# Lower_board.net
KiCad netlist of a schematic drawn in EAGLE
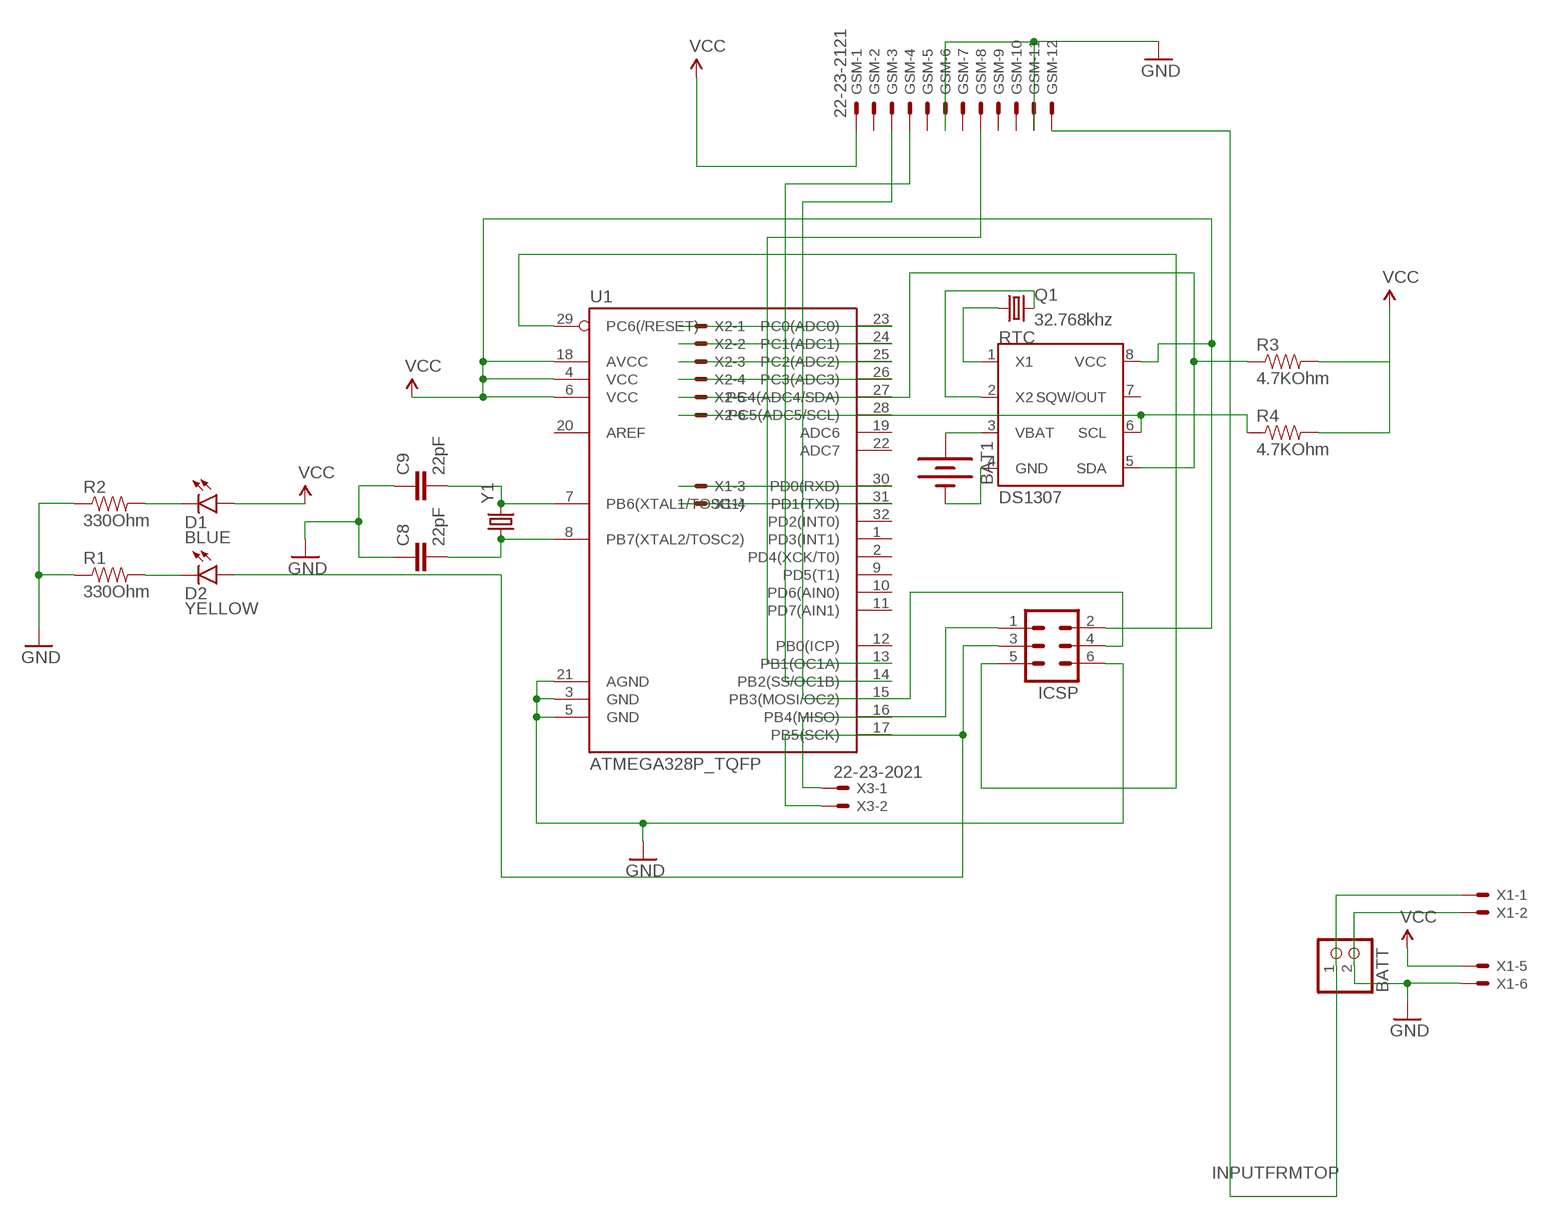
[diagram p0: schematic, sheet 1]

(export (version "E")
  (design (tool "Eeschema 10.0.6"))
  (components
    (comp (ref "BAT1")
      (value "BATTERY20PTH")
      (footprint "eagle-import:BATTCOM_20MM_PTH")
      (libsource (lib "eagle-import") (part "BATTERY20PTH"))
    )
    (comp (ref "BATT")
      (value "JST_2PIN-SMT-RA")
      (footprint "eagle-import:JST-PH-2-SMT-RA")
      (libsource (lib "eagle-import") (part "JST_2PIN-SMT-RA"))
    )
    (comp (ref "C8")
      (value "22pF")
      (footprint "eagle-import:0603-CAP")
      (libsource (lib "eagle-import") (part "CAP0603-CAP"))
    )
    (comp (ref "C9")
      (value "22pF")
      (footprint "eagle-import:0603-CAP")
      (libsource (lib "eagle-import") (part "CAP0603-CAP"))
    )
    (comp (ref "D1")
      (value "BLUE")
      (footprint "eagle-import:LED-1206")
      (libsource (lib "eagle-import") (part "LED-BLUE1206"))
    )
    (comp (ref "D2")
      (value "YELLOW")
      (footprint "eagle-import:LED-1206")
      (libsource (lib "eagle-import") (part "LED-YELLOWLARGE"))
    )
    (comp (ref "GSM")
      (value "22-23-2121")
      (footprint "eagle-import:22-23-2121")
      (fields (field (name "MF") "MOLEX"))
      (libsource (lib "eagle-import") (part "22-23-2121"))
    )
    (comp (ref "ICSP")
      (value "ML6")
      (footprint "eagle-import:ML6")
      (libsource (lib "eagle-import") (part "ML6"))
    )
    (comp (ref "Q1")
      (value "32.768khz")
      (footprint "eagle-import:CRYSTAL-TXC-7A")
      (libsource (lib "eagle-import") (part "CRYSTALTXC-7A"))
    )
    (comp (ref "R1")
      (value "330Ohm")
      (footprint "eagle-import:1206")
      (libsource (lib "eagle-import") (part "RESISTOR1206"))
    )
    (comp (ref "R2")
      (value "330Ohm")
      (footprint "eagle-import:1206")
      (libsource (lib "eagle-import") (part "RESISTOR1206"))
    )
    (comp (ref "R3")
      (value "4.7KOhm")
      (footprint "eagle-import:1206")
      (libsource (lib "eagle-import") (part "RESISTOR1206"))
    )
    (comp (ref "R4")
      (value "4.7KOhm")
      (footprint "eagle-import:1206")
      (libsource (lib "eagle-import") (part "RESISTOR1206"))
    )
    (comp (ref "RTC")
      (value "DS1307")
      (footprint "eagle-import:SOIC-8")
      (libsource (lib "eagle-import") (part "DS1307"))
    )
    (comp (ref "U1")
      (value "ATMEGA328P_TQFP")
      (footprint "eagle-import:TQFP32-08")
      (libsource (lib "eagle-import") (part "ATMEGA328P_TQFP"))
    )
    (comp (ref "X1")
      (value "22-23-2061")
      (footprint "eagle-import:22-23-2061")
      (fields (field (name "MF") "MOLEX"))
      (libsource (lib "eagle-import") (part "22-23-2061"))
    )
    (comp (ref "X2")
      (value "22-23-2061")
      (footprint "eagle-import:22-23-2061")
      (fields (field (name "MF") "MOLEX"))
      (libsource (lib "eagle-import") (part "22-23-2061"))
    )
    (comp (ref "X3")
      (value "22-23-2021")
      (footprint "eagle-import:22-23-2021")
      (fields (field (name "MF") "MOLEX"))
      (libsource (lib "eagle-import") (part "22-23-2021"))
    )
    (comp (ref "Y1")
      (value "CRYSTALTXC-7A")
      (footprint "eagle-import:CRYSTAL-TXC-7A")
      (libsource (lib "eagle-import") (part "CRYSTALTXC-7A"))
    )
  )
  (nets
    (net (code "1") (name "/INPUTFRMTOP") (class "Default")
      (node (ref "BATT") (pin "1") (pinfunction "2_1") (pintype "passive"))
      (node (ref "GSM") (pin "12") (pinfunction "S_12") (pintype "passive"))
      (node (ref "X1") (pin "1") (pinfunction "S_1") (pintype "passive"))
    )
    (net (code "2") (name "GND") (class "Default")
      (node (ref "BATT") (pin "2") (pinfunction "1_2") (pintype "passive"))
      (node (ref "C8") (pin "1") (pinfunction "1_1") (pintype "passive"))
      (node (ref "C9") (pin "1") (pinfunction "1_1") (pintype "passive"))
      (node (ref "GSM") (pin "11") (pinfunction "S_11") (pintype "passive"))
      (node (ref "GSM") (pin "6") (pinfunction "S_6") (pintype "passive"))
      (node (ref "ICSP") (pin "6") (pinfunction "6_6") (pintype "passive"))
      (node (ref "R1") (pin "1") (pinfunction "1_1") (pintype "passive"))
      (node (ref "R2") (pin "1") (pinfunction "1_1") (pintype "passive"))
      (node (ref "U1") (pin "21") (pinfunction "AGND_21") (pintype "bidirectional"))
      (node (ref "U1") (pin "3") (pinfunction "GND_3") (pintype "bidirectional"))
      (node (ref "U1") (pin "5") (pinfunction "GND_5") (pintype "bidirectional"))
      (node (ref "X1") (pin "2") (pinfunction "S_2") (pintype "passive"))
      (node (ref "X1") (pin "6") (pinfunction "S_6") (pintype "passive"))
    )
    (net (code "3") (name "Net-(BAT1-+)") (class "Default")
      (node (ref "BAT1") (pin "1") (pinfunction "+_1") (pintype "power_in"))
      (node (ref "RTC") (pin "3") (pinfunction "VBAT_3") (pintype "power_in"))
    )
    (net (code "4") (name "Net-(BAT1--)") (class "Default")
      (node (ref "BAT1") (pin "2") (pinfunction "-_2") (pintype "power_in"))
      (node (ref "RTC") (pin "4") (pinfunction "GND_4") (pintype "power_in"))
    )
    (net (code "5") (name "Net-(D1-PadC)") (class "Default")
      (node (ref "D1") (pin "C") (pinfunction "C_C") (pintype "passive"))
      (node (ref "R2") (pin "2") (pinfunction "2_2") (pintype "passive"))
    )
    (net (code "6") (name "Net-(D2-PadC)") (class "Default")
      (node (ref "D2") (pin "C") (pinfunction "C_C") (pintype "passive"))
      (node (ref "R1") (pin "2") (pinfunction "2_2") (pintype "passive"))
    )
    (net (code "7") (name "Net-(GSMF-S)") (class "Default")
      (node (ref "GSM") (pin "3") (pinfunction "S_3") (pintype "passive"))
      (node (ref "ICSP") (pin "4") (pinfunction "4_4") (pintype "passive"))
      (node (ref "U1") (pin "15") (pinfunction "PB3(MOSI/OC2)_15") (pintype "bidirectional"))
    )
    (net (code "8") (name "Net-(GSMG-S)") (class "Default")
      (node (ref "GSM") (pin "4") (pinfunction "S_4") (pintype "passive"))
      (node (ref "U1") (pin "14") (pinfunction "PB2(SS/OC1B)_14") (pintype "bidirectional"))
    )
    (net (code "9") (name "Net-(GSMK-S)") (class "Default")
      (node (ref "GSM") (pin "8") (pinfunction "S_8") (pintype "passive"))
      (node (ref "U1") (pin "13") (pinfunction "PB1(OC1A)_13") (pintype "bidirectional"))
    )
    (net (code "10") (name "Net-(Q1-1)") (class "Default")
      (node (ref "Q1") (pin "P$1") (pinfunction "1_P$1") (pintype "passive"))
      (node (ref "RTC") (pin "1") (pinfunction "X1_1") (pintype "input"))
    )
    (net (code "11") (name "Net-(Q1-2)") (class "Default")
      (node (ref "Q1") (pin "P$2") (pinfunction "2_P$2") (pintype "passive"))
      (node (ref "RTC") (pin "2") (pinfunction "X2_2") (pintype "output"))
    )
    (net (code "12") (name "Net-(RTC-SCL)") (class "Default")
      (node (ref "R4") (pin "1") (pinfunction "1_1") (pintype "passive"))
      (node (ref "RTC") (pin "6") (pinfunction "SCL_6") (pintype "input"))
      (node (ref "U1") (pin "28") (pinfunction "PC5(ADC5/SCL)_28") (pintype "bidirectional"))
      (node (ref "X2") (pin "6") (pinfunction "S_6") (pintype "passive"))
    )
    (net (code "13") (name "Net-(RTC-SDA)") (class "Default")
      (node (ref "R3") (pin "1") (pinfunction "1_1") (pintype "passive"))
      (node (ref "RTC") (pin "5") (pinfunction "SDA_5") (pintype "bidirectional"))
      (node (ref "U1") (pin "27") (pinfunction "PC4(ADC4/SDA)_27") (pintype "bidirectional"))
      (node (ref "X2") (pin "5") (pinfunction "S_5") (pintype "passive"))
    )
    (net (code "14") (name "Net-(U1-PB4(MISO))") (class "Default")
      (node (ref "ICSP") (pin "1") (pinfunction "1_1") (pintype "passive"))
      (node (ref "U1") (pin "16") (pinfunction "PB4(MISO)_16") (pintype "bidirectional"))
      (node (ref "X3") (pin "1") (pinfunction "S_1") (pintype "passive"))
    )
    (net (code "15") (name "Net-(U1-PB6(XTAL1{slash}TOSC1))") (class "Default")
      (node (ref "C9") (pin "2") (pinfunction "2_2") (pintype "passive"))
      (node (ref "U1") (pin "7") (pinfunction "PB6(XTAL1/TOSC1)_7") (pintype "bidirectional"))
      (node (ref "Y1") (pin "P$2") (pinfunction "2_P$2") (pintype "passive"))
    )
    (net (code "16") (name "Net-(U1-PB7(XTAL2{slash}TOSC2))") (class "Default")
      (node (ref "C8") (pin "2") (pinfunction "2_2") (pintype "passive"))
      (node (ref "U1") (pin "8") (pinfunction "PB7(XTAL2/TOSC2)_8") (pintype "bidirectional"))
      (node (ref "Y1") (pin "P$1") (pinfunction "1_P$1") (pintype "passive"))
    )
    (net (code "17") (name "Net-(U1-PC0(ADC0))") (class "Default")
      (node (ref "U1") (pin "23") (pinfunction "PC0(ADC0)_23") (pintype "bidirectional"))
      (node (ref "X2") (pin "1") (pinfunction "S_1") (pintype "passive"))
    )
    (net (code "18") (name "Net-(U1-PC1(ADC1))") (class "Default")
      (node (ref "U1") (pin "24") (pinfunction "PC1(ADC1)_24") (pintype "bidirectional"))
      (node (ref "X2") (pin "2") (pinfunction "S_2") (pintype "passive"))
    )
    (net (code "19") (name "Net-(U1-PC2(ADC2))") (class "Default")
      (node (ref "U1") (pin "25") (pinfunction "PC2(ADC2)_25") (pintype "bidirectional"))
      (node (ref "X2") (pin "3") (pinfunction "S_3") (pintype "passive"))
    )
    (net (code "20") (name "Net-(U1-PC3(ADC3))") (class "Default")
      (node (ref "U1") (pin "26") (pinfunction "PC3(ADC3)_26") (pintype "bidirectional"))
      (node (ref "X2") (pin "4") (pinfunction "S_4") (pintype "passive"))
    )
    (net (code "21") (name "Net-(U1-PC6({slash}RESET))") (class "Default")
      (node (ref "ICSP") (pin "5") (pinfunction "5_5") (pintype "passive"))
      (node (ref "U1") (pin "29") (pinfunction "PC6(/RESET)_29") (pintype "bidirectional"))
    )
    (net (code "22") (name "Net-(U1-PD0(RXD))") (class "Default")
      (node (ref "U1") (pin "30") (pinfunction "PD0(RXD)_30") (pintype "bidirectional"))
      (node (ref "X1") (pin "3") (pinfunction "S_3") (pintype "passive"))
    )
    (net (code "23") (name "Net-(U1-PD1(TXD))") (class "Default")
      (node (ref "U1") (pin "31") (pinfunction "PD1(TXD)_31") (pintype "bidirectional"))
      (node (ref "X1") (pin "4") (pinfunction "S_4") (pintype "passive"))
    )
    (net (code "24") (name "Net-(X3B-S)") (class "Default")
      (node (ref "D2") (pin "A") (pinfunction "A_A") (pintype "passive"))
      (node (ref "ICSP") (pin "3") (pinfunction "3_3") (pintype "passive"))
      (node (ref "X3") (pin "2") (pinfunction "S_2") (pintype "passive"))
    )
    (net (code "25") (name "VCC") (class "Default")
      (node (ref "D1") (pin "A") (pinfunction "A_A") (pintype "passive"))
      (node (ref "GSM") (pin "1") (pinfunction "S_1") (pintype "passive"))
      (node (ref "ICSP") (pin "2") (pinfunction "2_2") (pintype "passive"))
      (node (ref "R3") (pin "2") (pinfunction "2_2") (pintype "passive"))
      (node (ref "R4") (pin "2") (pinfunction "2_2") (pintype "passive"))
      (node (ref "RTC") (pin "8") (pinfunction "VCC_8") (pintype "power_in"))
      (node (ref "U1") (pin "18") (pinfunction "AVCC_18") (pintype "bidirectional"))
      (node (ref "U1") (pin "4") (pinfunction "VCC_4") (pintype "bidirectional"))
      (node (ref "U1") (pin "6") (pinfunction "VCC_6") (pintype "bidirectional"))
      (node (ref "X1") (pin "5") (pinfunction "S_5") (pintype "passive"))
    )
    (net (code "26") (name "unconnected-(GSMB-S-Pad10)") (class "Default")
      (node (ref "GSM") (pin "10") (pinfunction "S_10") (pintype "passive"))
    )
    (net (code "27") (name "unconnected-(GSME-S-Pad2)") (class "Default")
      (node (ref "GSM") (pin "2") (pinfunction "S_2") (pintype "passive"))
    )
    (net (code "28") (name "unconnected-(GSMH-S-Pad5)") (class "Default")
      (node (ref "GSM") (pin "5") (pinfunction "S_5") (pintype "passive"))
    )
    (net (code "29") (name "unconnected-(GSMJ-S-Pad7)") (class "Default")
      (node (ref "GSM") (pin "7") (pinfunction "S_7") (pintype "passive"))
    )
    (net (code "30") (name "unconnected-(GSML-S-Pad9)") (class "Default")
      (node (ref "GSM") (pin "9") (pinfunction "S_9") (pintype "passive"))
    )
    (net (code "31") (name "unconnected-(RTC-SQW{slash}OUT-Pad7)") (class "Default")
      (node (ref "RTC") (pin "7") (pinfunction "SQW/OUT_7") (pintype "output"))
    )
    (net (code "32") (name "unconnected-(U1-ADC6-Pad19)") (class "Default")
      (node (ref "U1") (pin "19") (pinfunction "ADC6_19") (pintype "bidirectional"))
    )
    (net (code "33") (name "unconnected-(U1-ADC7-Pad22)") (class "Default")
      (node (ref "U1") (pin "22") (pinfunction "ADC7_22") (pintype "bidirectional"))
    )
    (net (code "34") (name "unconnected-(U1-AREF-Pad20)") (class "Default")
      (node (ref "U1") (pin "20") (pinfunction "AREF_20") (pintype "bidirectional"))
    )
    (net (code "35") (name "unconnected-(U1-PB0(ICP)-Pad12)") (class "Default")
      (node (ref "U1") (pin "12") (pinfunction "PB0(ICP)_12") (pintype "bidirectional"))
    )
    (net (code "36") (name "unconnected-(U1-PB5(SCK)-Pad17)") (class "Default")
      (node (ref "U1") (pin "17") (pinfunction "PB5(SCK)_17") (pintype "bidirectional"))
    )
    (net (code "37") (name "unconnected-(U1-PD2(INT0)-Pad32)") (class "Default")
      (node (ref "U1") (pin "32") (pinfunction "PD2(INT0)_32") (pintype "bidirectional"))
    )
    (net (code "38") (name "unconnected-(U1-PD3(INT1)-Pad1)") (class "Default")
      (node (ref "U1") (pin "1") (pinfunction "PD3(INT1)_1") (pintype "bidirectional"))
    )
    (net (code "39") (name "unconnected-(U1-PD4(XCK{slash}T0)-Pad2)") (class "Default")
      (node (ref "U1") (pin "2") (pinfunction "PD4(XCK/T0)_2") (pintype "bidirectional"))
    )
    (net (code "40") (name "unconnected-(U1-PD5(T1)-Pad9)") (class "Default")
      (node (ref "U1") (pin "9") (pinfunction "PD5(T1)_9") (pintype "bidirectional"))
    )
    (net (code "41") (name "unconnected-(U1-PD6(AIN0)-Pad10)") (class "Default")
      (node (ref "U1") (pin "10") (pinfunction "PD6(AIN0)_10") (pintype "bidirectional"))
    )
    (net (code "42") (name "unconnected-(U1-PD7(AIN1)-Pad11)") (class "Default")
      (node (ref "U1") (pin "11") (pinfunction "PD7(AIN1)_11") (pintype "bidirectional"))
    )
  )
)
